# Input.net
KiCad netlist of a schematic drawn in Altium Designer
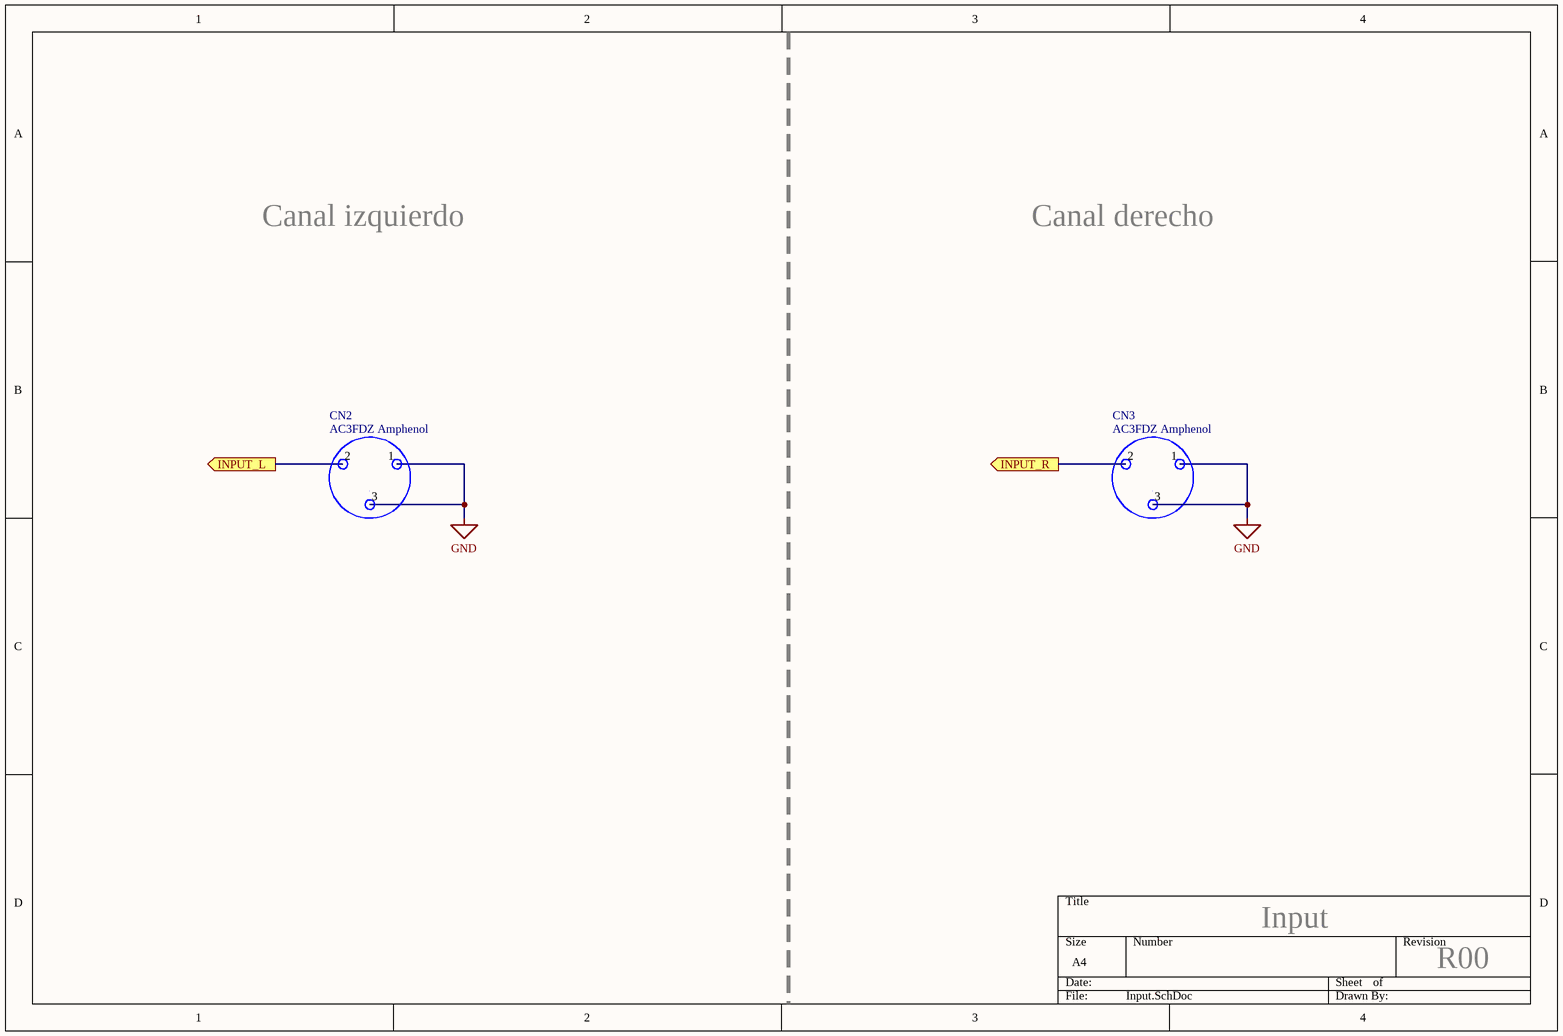
[diagram p0: Input.SchDoc]

(export (version "E")
  (design (tool "Eeschema 10.0.6"))
  (components
    (comp (ref "CN2")
      (value "AC3FDZ Amphenol")
      (footprint "XLR_Ext")
      (description "XLR connector (canon) hembra")
      (libsource (lib "Radios_Comunitarias") (part "XLR_hembra"))
    )
    (comp (ref "CN3")
      (value "AC3FDZ Amphenol")
      (footprint "XLR_Ext")
      (description "XLR connector (canon) hembra")
      (libsource (lib "Radios_Comunitarias") (part "XLR_hembra"))
    )
  )
  (nets
    (net (code "1") (name "/INPUT_L") (class "Default")
      (node (ref "CN2") (pin "2") (pinfunction "Hot_2") (pintype "passive"))
    )
    (net (code "2") (name "/INPUT_R") (class "Default")
      (node (ref "CN3") (pin "2") (pinfunction "Hot_2") (pintype "passive"))
    )
    (net (code "3") (name "GND") (class "Default")
      (node (ref "CN2") (pin "1") (pinfunction "Chasis_1") (pintype "passive"))
      (node (ref "CN2") (pin "3") (pinfunction "Cold_3") (pintype "passive"))
      (node (ref "CN3") (pin "1") (pinfunction "Chasis_1") (pintype "passive"))
      (node (ref "CN3") (pin "3") (pinfunction "Cold_3") (pintype "passive"))
    )
  )
)
